# GPS_tracker_PWR.net
KiCad netlist of a schematic drawn in Altium Designer
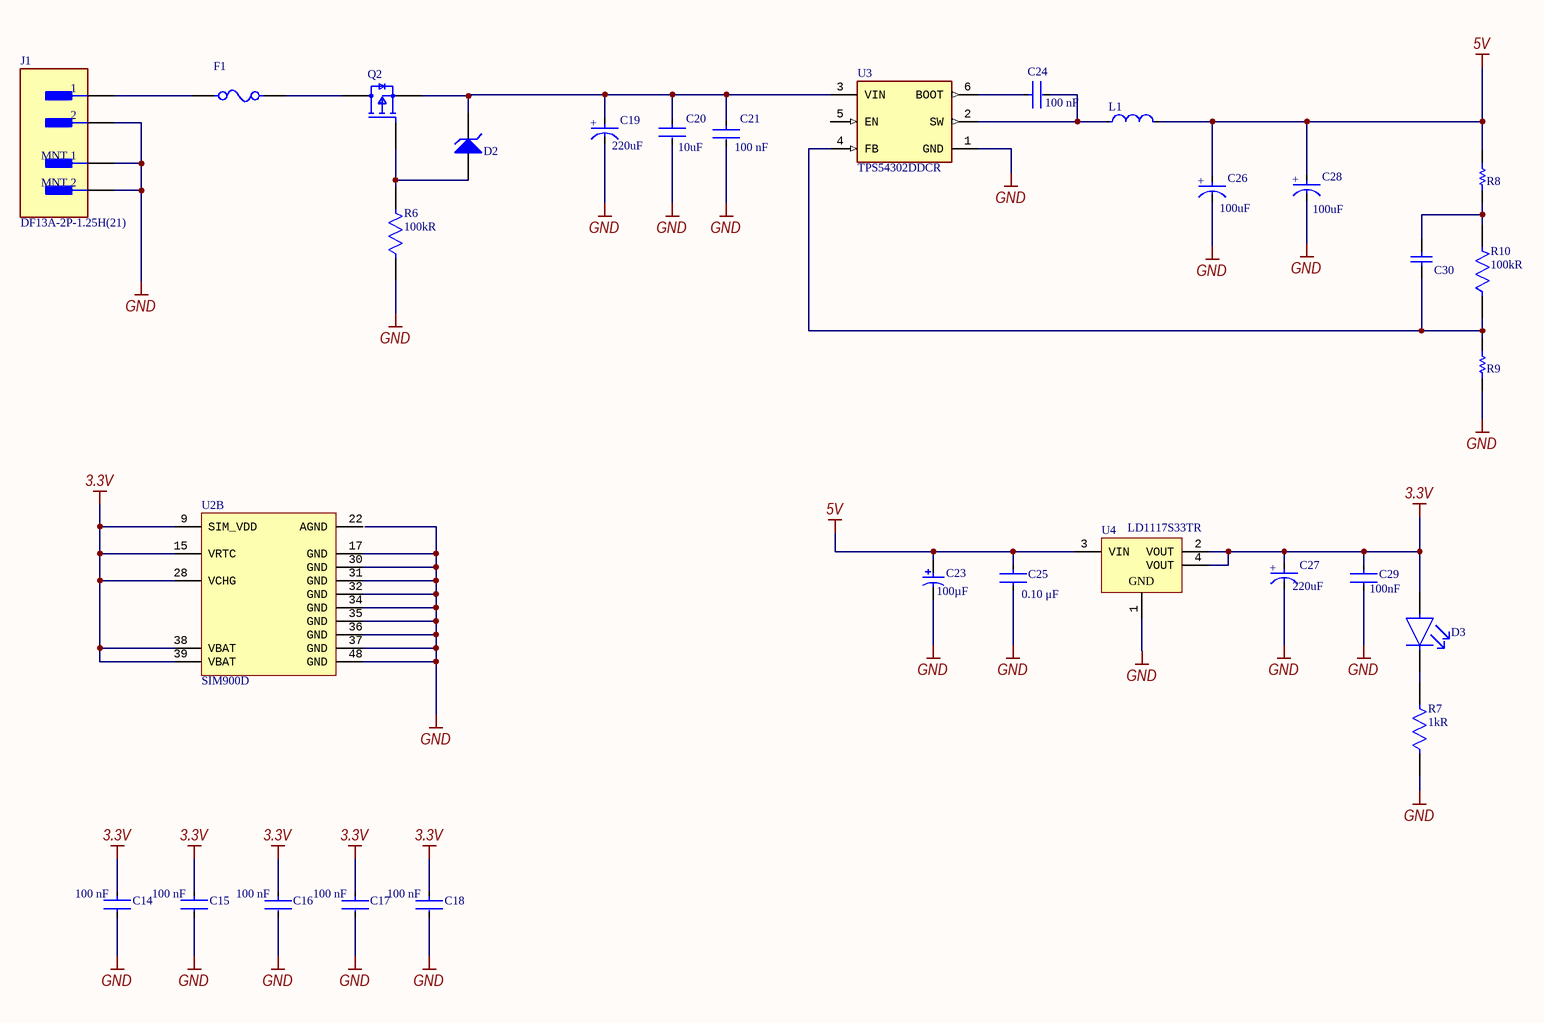
[diagram p0: GPS_tracker PWR.SchDoc]

(export (version "E")
  (design (tool "Eeschema 10.0.6"))
  (components
    (comp (ref "C14")
      (value "CC0603KRX7R7BB104")
      (footprint "FP-CC0603-DA-MFG")
      (description "CAP CER 0.1UF 16V X7R 0603")
      (fields
        (field (name "OCTOPART") "https://octopart.com/cc0603krx7r7bb104-yageo-192941")
        (field (name "TOLERANCE") "0.1")
        (field (name "CAPACITANCE") "100 nF")
      )
      (libsource (lib "Altium Content Vault") (part "11868f565c42a9108669ba33697ecf6"))
    )
    (comp (ref "C15")
      (value "CC0603KRX7R7BB104")
      (footprint "FP-CC0603-DA-MFG")
      (description "CAP CER 0.1UF 16V X7R 0603")
      (fields
        (field (name "OCTOPART") "https://octopart.com/cc0603krx7r7bb104-yageo-192941")
        (field (name "TOLERANCE") "0.1")
        (field (name "CAPACITANCE") "100 nF")
      )
      (libsource (lib "Altium Content Vault") (part "11868f565c42a9108669ba33697ecf6"))
    )
    (comp (ref "C16")
      (value "CC0603KRX7R7BB104")
      (footprint "FP-CC0603-DA-MFG")
      (description "CAP CER 0.1UF 16V X7R 0603")
      (fields
        (field (name "OCTOPART") "https://octopart.com/cc0603krx7r7bb104-yageo-192941")
        (field (name "TOLERANCE") "0.1")
        (field (name "CAPACITANCE") "100 nF")
      )
      (libsource (lib "Altium Content Vault") (part "11868f565c42a9108669ba33697ecf6"))
    )
    (comp (ref "C17")
      (value "CC0603KRX7R7BB104")
      (footprint "FP-CC0603-DA-MFG")
      (description "CAP CER 0.1UF 16V X7R 0603")
      (fields
        (field (name "OCTOPART") "https://octopart.com/cc0603krx7r7bb104-yageo-192941")
        (field (name "TOLERANCE") "0.1")
        (field (name "CAPACITANCE") "100 nF")
      )
      (libsource (lib "Altium Content Vault") (part "11868f565c42a9108669ba33697ecf6"))
    )
    (comp (ref "C18")
      (value "CC0603KRX7R7BB104")
      (footprint "FP-CC0603-DA-MFG")
      (description "CAP CER 0.1UF 16V X7R 0603")
      (fields
        (field (name "OCTOPART") "https://octopart.com/cc0603krx7r7bb104-yageo-192941")
        (field (name "TOLERANCE") "0.1")
        (field (name "CAPACITANCE") "100 nF")
      )
      (libsource (lib "Altium Content Vault") (part "11868f565c42a9108669ba33697ecf6"))
    )
    (comp (ref "C19")
      (value "EEEFK1V221P")
      (footprint "FP-FKF-MFG")
      (description "CAP ALUM 220UF 20% 35V SMD")
      (fields
        (field (name "VOLTAGE") "35V")
        (field (name "CAPACITANCE") "220uF")
        (field (name "TOLERANCE") "20%")
      )
      (libsource (lib "Altium Content Vault") (part "a00bbbee19879c290e62620ae7e47b1"))
    )
    (comp (ref "C20")
      (value "CL32B106KBJNNNE")
      (footprint "FP-CL32-IPC_C")
      (description "Cap Ceramic 10uF 50V X7R ±10% SMD 1210 +125°C Embossed T/R")
      (fields
        (field (name "CAPACITANCE") "10uF")
        (field (name "TOLERANCE") "10%")
        (field (name "VOLTAGE") "50V")
      )
      (libsource (lib "Altium Content Vault") (part "b4654b650e69147ec39a6b967a45e02"))
    )
    (comp (ref "C21")
      (value "CC0603KRX7R7BB104")
      (footprint "FP-CC0603-DA-MFG")
      (description "CAP CER 0.1UF 16V X7R 0603")
      (fields
        (field (name "OCTOPART") "https://octopart.com/cc0603krx7r7bb104-yageo-192941")
        (field (name "TOLERANCE") "0.1")
        (field (name "CAPACITANCE") "100 nF")
      )
      (libsource (lib "Altium Content Vault") (part "11868f565c42a9108669ba33697ecf6"))
    )
    (comp (ref "C23")
      (value "EEEFK1C101P")
      (footprint "PNSC-EEEFK1C101P_L")
      (fields (field (name "MANUFACTURER") "Panasonic") (field (name "CAPACITANCE") "100µF"))
      (libsource (lib "Altium Content Vault") (part "CAP-P-2"))
    )
    (comp (ref "C24")
      (value "CC0603KRX7R7BB104")
      (footprint "FP-CC0603-DA-MFG")
      (description "CAP CER 0.1UF 16V X7R 0603")
      (fields
        (field (name "OCTOPART") "https://octopart.com/cc0603krx7r7bb104-yageo-192941")
        (field (name "TOLERANCE") "0.1")
        (field (name "CAPACITANCE") "100 nF")
      )
      (libsource (lib "Altium Content Vault") (part "11868f565c42a9108669ba33697ecf6"))
    )
    (comp (ref "C25")
      (value "0.10 μF")
      (footprint "FP-C0805C-DN-MFG")
      (description "CAP CER 0.1UF 50V X7R 0805")
      (fields
        (field (name "MANUFACTURER PART NUMBER") "C0805C104K5RACTU")
        (field (name "MANUFACTURER") "KEMET")
      )
      (libsource (lib "Altium Content Vault") (part "b4654b650e69147ec39a6b967a45e02"))
    )
    (comp (ref "C26")
      (value "T521D107M025ATE040")
      (footprint "FP-T521D107M025ATE040-MFG")
      (description "CAP TANT POLY 100UF 25V 2917")
      (fields (field (name "TOLERANCE") "20%") (field (name "CAPACITANCE") "100uF"))
      (libsource (lib "Altium Content Vault") (part "a00bbbee19879c290e62620ae7e47b1"))
    )
    (comp (ref "C27")
      (value "TAJC227K006RNJ")
      (footprint "FP-TAJC-MFG")
      (description "220uF 6.3V  ±10% 1.2Ω 2312  SMD Tantalum Capacitor")
      (fields
        (field (name "TOLERANCE") "10%")
        (field (name "VOLTAGE") "6.3V")
        (field (name "CAPACITANCE") "220uF")
      )
      (libsource (lib "Altium Content Vault") (part "203bc49f2ac43e59fd269a8c329ed05"))
    )
    (comp (ref "C28")
      (value "T521D107M025ATE040")
      (footprint "FP-T521D107M025ATE040-MFG")
      (description "CAP TANT POLY 100UF 25V 2917")
      (fields (field (name "TOLERANCE") "20%") (field (name "CAPACITANCE") "100uF"))
      (libsource (lib "Altium Content Vault") (part "a00bbbee19879c290e62620ae7e47b1"))
    )
    (comp (ref "C29")
      (value "C0603X104K5RACTU")
      (footprint "FP-C0603-CJ-MFG")
      (description "CAP CER 0.1UF 50V X7R 0603")
      (fields
        (field (name "VOLTAGE") "50V")
        (field (name "CAPACITANCE") "100nF")
        (field (name "MANUFACTURER") "Kemet")
      )
      (libsource (lib "Altium Content Vault") (part "11868f565c42a9108669ba33697ecf6"))
    )
    (comp (ref "C30")
      (value "06035A750JAT2A")
      (footprint "CAPC1608X90X35ML15T15")
      (fields (field (name "MANUFACTURER") "AVX Interconnect / Elco"))
      (libsource (lib "Altium Content Vault") (part "CAP"))
    )
    (comp (ref "D2")
      (value "MMSZ4699T1G")
      (footprint "ONSC-SOD-123-2-425-04_V")
      (description "Zener Voltage Regulator, 500 mW, 2-Pin SOD-123, Pb-Free, Tape and Reel")
      (fields (field (name "MANUFACTURER") "On Semiconductor"))
      (libsource (lib "Altium Content Vault") (part "ONSC-K1A2-2"))
    )
    (comp (ref "D3")
      (value "SML-D12P8WT86C")
      (footprint "FP-SML-D12-MFG")
      (description "LED GREEN 1608 SMD")
      (fields
        (field (name "OCTOPART") "https://octopart.com/sml-d12p8wt86c-rohm-77740213")
        (field (name "MANUFACTURER") "Rohm")
      )
      (libsource (lib "Altium Content Vault") (part "8706943c75ba83719d021d2fdc84c58"))
    )
    (comp (ref "F1")
      (value "0452001.MRL")
      (footprint "FP-0452-MFG")
      (description "FUSE BRD MNT 1A 125VAC/VDC 2SMD")
      (fields
        (field (name "MANUFACTURER") "Littelfuse Inc")
        (field (name "OCTOPART") "https://octopart.com/0452001.mrl-littelfuse-566112")
      )
      (libsource (lib "Altium Content Vault") (part "5bcf9b9f640e542cf0359d10258e979"))
    )
    (comp (ref "J1")
      (value "DF13A-2P-1.25H(21)")
      (footprint "FP-DF13A-2P-1_25H_21-MFG")
      (description "CONN HEADER SMD R/A 2POS 1.25MM")
      (fields
        (field (name "MANUFACTURER") "Hirose")
        (field (name "OCTOPART") "https://octopart.com/df13a-2p-1.25h%2821%29-hirose-24789905")
      )
      (libsource (lib "Altium Content Vault") (part "56ec3178a87b3978bdc1b3682cd516a"))
    )
    (comp (ref "L1")
      (value "IHLP2525CZER100M11")
      (footprint "FP-IHLP-2525CZ-FP_2_413x3-MFG")
      (description "Commercial Inductors, Low DCR Series 10uH 4A 71.2mΩ 20%")
      (fields (field (name "TOLERANCE") "20%"))
      (libsource (lib "Altium Content Vault") (part "725321dda6339637d4d059423bc1c3c"))
    )
    (comp (ref "Q2")
      (value "DMP3099L-7")
      (footprint "FP-SOT23-IPC_B")
      (description "MOSFET P-CH 30V SOT23")
      (libsource (lib "Altium Content Vault") (part "d876440acba04c58a9f817a20952145"))
    )
    (comp (ref "R6")
      (value "RC0603FR-07100KL")
      (footprint "FP-RC0603-0_55-MFG")
      (description "RES SMD 100K OHM 1% 1/10W 0603")
      (fields (field (name "RESISTANCE") "100kR") (field (name "TOLERANCE") "1%"))
      (libsource (lib "Altium Content Vault") (part "1029c3af85768c4190bb7ad29bc67b5"))
    )
    (comp (ref "R7")
      (value "CRCW06031K00FKEA")
      (footprint "FP-CRCW0603-e3-MFG")
      (description "RES Thick Film, 1kΩ, 1%, 0.1W, 100ppm/°C, 0603")
      (fields (field (name "TOLERANCE") "1%") (field (name "RESISTANCE") "1kR"))
      (libsource (lib "Altium Content Vault") (part "1029c3af85768c4190bb7ad29bc67b5"))
    )
    (comp (ref "R8")
      (value "RC0603FR-0749R9L")
      (footprint "RESC1608X55X25NL10T15")
      (libsource (lib "Altium Content Vault") (part "RES-2"))
    )
    (comp (ref "R9")
      (value "ERJ-3EKF1332V")
      (footprint "RESC1608X55X30LL15T15")
      (fields (field (name "MANUFACTURER") "Panasonic"))
      (libsource (lib "Altium Content Vault") (part "RES"))
    )
    (comp (ref "R10")
      (value "RC0603FR-07100KL")
      (footprint "FP-RC0603-0_55-MFG")
      (description "RES SMD 100K OHM 1% 1/10W 0603")
      (fields (field (name "RESISTANCE") "100kR") (field (name "TOLERANCE") "1%"))
      (libsource (lib "Altium Content Vault") (part "1029c3af85768c4190bb7ad29bc67b5"))
    )
    (comp (ref "U2")
      (value "SIM900D")
      (footprint "SIMC-SIM900D_V")
      (fields (field (name "MANUFACTURER") "SIM Com"))
      (libsource (lib "Altium Content Vault") (part "SIMC-SIM900D-48"))
    )
    (comp (ref "U3")
      (value "TPS54302DDCR")
      (footprint "FP-DDC0006A-MFG")
      (description "IC REG BUCK ADJ 3A TSOT23-6")
      (fields
        (field (name "MANUFACTURER") "Texas Instruments")
        (field (name "OCTOPART") "https://octopart.com/tps54302ddcr-texas+instruments-74209025")
      )
      (libsource (lib "Altium Content Vault") (part "e6e62595b56d4ede9a2c24ebe42f01f"))
    )
    (comp (ref "U4")
      (value "LD1117S33TR")
      (footprint "SOT-223_L")
      (description "Fixed Low Drop Positive Voltage Regulator, 3.3V, 4-Pin SOT-223, Tape and Reel")
      (libsource (lib "Altium Content Vault") (part "PM-REG-LD1117-SOT4"))
    )
  )
  (nets
    (net (code "1") (name "3.3V") (class "Default")
      (node (ref "C14") (pin "1") (pinfunction "1_1") (pintype "passive"))
      (node (ref "C15") (pin "1") (pinfunction "1_1") (pintype "passive"))
      (node (ref "C16") (pin "1") (pinfunction "1_1") (pintype "passive"))
      (node (ref "C17") (pin "1") (pinfunction "1_1") (pintype "passive"))
      (node (ref "C18") (pin "1") (pinfunction "1_1") (pintype "passive"))
      (node (ref "C27") (pin "2") (pinfunction "A_2") (pintype "passive"))
      (node (ref "C29") (pin "1") (pinfunction "1_1") (pintype "passive"))
      (node (ref "D3") (pin "2") (pinfunction "A_2") (pintype "passive"))
      (node (ref "U2") (pin "15") (pinfunction "VRTC_15") (pintype "power_in"))
      (node (ref "U2") (pin "28") (pinfunction "VCHG_28") (pintype "power_in"))
      (node (ref "U2") (pin "38") (pinfunction "VBAT_38") (pintype "power_in"))
      (node (ref "U2") (pin "39") (pinfunction "VBAT_39") (pintype "power_in"))
      (node (ref "U2") (pin "9") (pinfunction "SIM_VDD_9") (pintype "power_in"))
      (node (ref "U4") (pin "2") (pinfunction "VOUT_2") (pintype "power_in"))
      (node (ref "U4") (pin "4") (pinfunction "VOUT_4") (pintype "power_in"))
    )
    (net (code "2") (name "5V") (class "Default")
      (node (ref "C23") (pin "1") (pinfunction "1_1") (pintype "passive"))
      (node (ref "C25") (pin "1") (pinfunction "1_1") (pintype "passive"))
      (node (ref "C26") (pin "2") (pinfunction "A_2") (pintype "passive"))
      (node (ref "C28") (pin "2") (pinfunction "A_2") (pintype "passive"))
      (node (ref "L1") (pin "2") (pinfunction "2_2") (pintype "passive"))
      (node (ref "R8") (pin "2") (pinfunction "2_2") (pintype "passive"))
      (node (ref "U4") (pin "3") (pinfunction "VIN_3") (pintype "power_in"))
    )
    (net (code "3") (name "GND") (class "Default")
      (node (ref "C14") (pin "2") (pinfunction "2_2") (pintype "passive"))
      (node (ref "C15") (pin "2") (pinfunction "2_2") (pintype "passive"))
      (node (ref "C16") (pin "2") (pinfunction "2_2") (pintype "passive"))
      (node (ref "C17") (pin "2") (pinfunction "2_2") (pintype "passive"))
      (node (ref "C18") (pin "2") (pinfunction "2_2") (pintype "passive"))
      (node (ref "C19") (pin "1") (pinfunction "C_1") (pintype "passive"))
      (node (ref "C20") (pin "2") (pinfunction "2_2") (pintype "passive"))
      (node (ref "C21") (pin "2") (pinfunction "2_2") (pintype "passive"))
      (node (ref "C23") (pin "2") (pinfunction "2_2") (pintype "passive"))
      (node (ref "C25") (pin "2") (pinfunction "2_2") (pintype "passive"))
      (node (ref "C26") (pin "1") (pinfunction "C_1") (pintype "passive"))
      (node (ref "C27") (pin "1") (pinfunction "C_1") (pintype "passive"))
      (node (ref "C28") (pin "1") (pinfunction "C_1") (pintype "passive"))
      (node (ref "C29") (pin "2") (pinfunction "2_2") (pintype "passive"))
      (node (ref "J1") (pin "2") (pinfunction "2_2") (pintype "passive"))
      (node (ref "J1") (pin "3") (pinfunction "MNT_1_3") (pintype "passive"))
      (node (ref "J1") (pin "4") (pinfunction "MNT_2_4") (pintype "passive"))
      (node (ref "R6") (pin "1") (pinfunction "1_1") (pintype "passive"))
      (node (ref "R7") (pin "1") (pinfunction "1_1") (pintype "passive"))
      (node (ref "R9") (pin "1") (pinfunction "1_1") (pintype "passive"))
      (node (ref "U2") (pin "17") (pinfunction "GND_17") (pintype "power_in"))
      (node (ref "U2") (pin "30") (pinfunction "GND_30") (pintype "power_in"))
      (node (ref "U2") (pin "31") (pinfunction "GND_31") (pintype "power_in"))
      (node (ref "U2") (pin "32") (pinfunction "GND_32") (pintype "power_in"))
      (node (ref "U2") (pin "34") (pinfunction "GND_34") (pintype "power_in"))
      (node (ref "U2") (pin "35") (pinfunction "GND_35") (pintype "power_in"))
      (node (ref "U2") (pin "36") (pinfunction "GND_36") (pintype "power_in"))
      (node (ref "U2") (pin "37") (pinfunction "GND_37") (pintype "power_in"))
      (node (ref "U2") (pin "48") (pinfunction "GND_48") (pintype "power_in"))
      (node (ref "U3") (pin "1") (pinfunction "GND_1") (pintype "power_in"))
      (node (ref "U4") (pin "1") (pinfunction "GND_1") (pintype "power_in"))
    )
    (net (code "4") (name "Net-(C19-A)") (class "Default")
      (node (ref "C19") (pin "2") (pinfunction "A_2") (pintype "passive"))
      (node (ref "C20") (pin "1") (pinfunction "1_1") (pintype "passive"))
      (node (ref "C21") (pin "1") (pinfunction "1_1") (pintype "passive"))
      (node (ref "D2") (pin "1") (pinfunction "K_1") (pintype "passive"))
      (node (ref "Q2") (pin "2") (pinfunction "S_2") (pintype "passive"))
      (node (ref "U3") (pin "3") (pinfunction "VIN_3") (pintype "power_in"))
    )
    (net (code "5") (name "Net-(C30-Pad2)") (class "Default")
      (node (ref "C30") (pin "2") (pinfunction "2_2") (pintype "passive"))
      (node (ref "R10") (pin "2") (pinfunction "2_2") (pintype "passive"))
      (node (ref "R8") (pin "1") (pinfunction "1_1") (pintype "passive"))
    )
    (net (code "6") (name "Net-(D2-A)") (class "Default")
      (node (ref "D2") (pin "2") (pinfunction "A_2") (pintype "passive"))
      (node (ref "Q2") (pin "1") (pinfunction "G_1") (pintype "passive"))
      (node (ref "R6") (pin "2") (pinfunction "2_2") (pintype "passive"))
    )
    (net (code "7") (name "Net-(D3-C)") (class "Default")
      (node (ref "D3") (pin "1") (pinfunction "C_1") (pintype "passive"))
      (node (ref "R7") (pin "2") (pinfunction "2_2") (pintype "passive"))
    )
    (net (code "8") (name "Net-(F1-Pad1)") (class "Default")
      (node (ref "F1") (pin "1") (pinfunction "1_1") (pintype "passive"))
      (node (ref "J1") (pin "1") (pinfunction "1_1") (pintype "passive"))
    )
    (net (code "9") (name "Net-(Q2-D)") (class "Default")
      (node (ref "F1") (pin "2") (pinfunction "2_2") (pintype "passive"))
      (node (ref "Q2") (pin "3") (pinfunction "D_3") (pintype "passive"))
    )
    (net (code "10") (name "Net-(U3-BOOT)") (class "Default")
      (node (ref "C24") (pin "1") (pinfunction "1_1") (pintype "passive"))
      (node (ref "U3") (pin "6") (pinfunction "BOOT_6") (pintype "output"))
    )
    (net (code "11") (name "Net-(U3-FB)") (class "Default")
      (node (ref "C30") (pin "1") (pinfunction "1_1") (pintype "passive"))
      (node (ref "R10") (pin "1") (pinfunction "1_1") (pintype "passive"))
      (node (ref "R9") (pin "2") (pinfunction "2_2") (pintype "passive"))
      (node (ref "U3") (pin "4") (pinfunction "FB_4") (pintype "input"))
    )
    (net (code "12") (name "Net-(U3-SW)") (class "Default")
      (node (ref "C24") (pin "2") (pinfunction "2_2") (pintype "passive"))
      (node (ref "L1") (pin "1") (pinfunction "1_1") (pintype "passive"))
      (node (ref "U3") (pin "2") (pinfunction "SW_2") (pintype "output"))
    )
    (net (code "13") (name "unconnected-(U2B-AGND-Pad22)") (class "Default")
      (node (ref "U2") (pin "22") (pinfunction "AGND_22") (pintype "power_in"))
    )
    (net (code "14") (name "unconnected-(U3-EN-Pad5)") (class "Default")
      (node (ref "U3") (pin "5") (pinfunction "EN_5") (pintype "input"))
    )
  )
)
